# schematic.net
KiCad netlist of a schematic drawn in Altium Designer
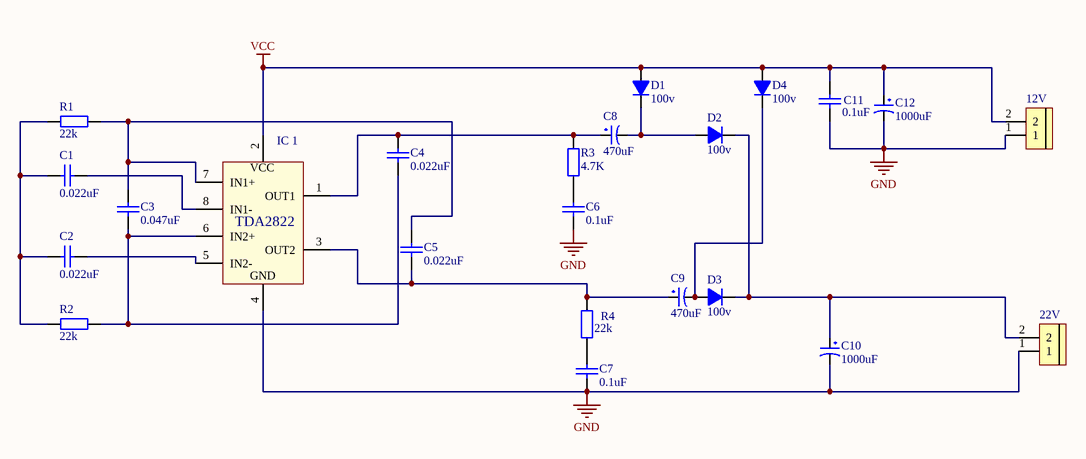
[diagram p0: schematic.SchDoc]

(export (version "E")
  (design (tool "Eeschema 10.0.6"))
  (components
    (comp (ref "12V")
      (value "~")
      (footprint "Con 2 KF301 5.08")
      (description "Cắm")
      (libsource (lib "Connector") (part "CON 2 KF301"))
    )
    (comp (ref "22V")
      (value "~")
      (footprint "Con 2 KF301 5.08")
      (description "Cắm")
      (libsource (lib "Connector") (part "CON 2 KF301"))
    )
    (comp (ref "C1")
      (value "0.022uF")
      (footprint "tu gom")
      (description "Cắm")
      (libsource (lib "Capacitor") (part "Tu gom 104 50V"))
    )
    (comp (ref "C2")
      (value "0.022uF")
      (footprint "tu gom")
      (description "Cắm")
      (libsource (lib "Capacitor") (part "Tu gom 104 50V"))
    )
    (comp (ref "C3")
      (value "0.047uF")
      (footprint "tu gom")
      (description "Cắm")
      (libsource (lib "Capacitor") (part "Tu gom 104 50V"))
    )
    (comp (ref "C4")
      (value "0.022uF")
      (footprint "tu gom")
      (description "Cắm")
      (libsource (lib "Capacitor") (part "Tu gom 104 50V"))
    )
    (comp (ref "C5")
      (value "0.022uF")
      (footprint "tu gom")
      (description "Cắm")
      (libsource (lib "Capacitor") (part "Tu gom 104 50V"))
    )
    (comp (ref "C6")
      (value "0.1uF")
      (footprint "tu gom")
      (description "Cắm")
      (libsource (lib "Capacitor") (part "Tu gom 104 50V"))
    )
    (comp (ref "C7")
      (value "0.1uF")
      (footprint "tu gom")
      (description "Cắm")
      (libsource (lib "Capacitor") (part "Tu gom 104 50V"))
    )
    (comp (ref "C8")
      (value "470uF")
      (footprint "tu hoa 13mm")
      (description "Cắm")
      (libsource (lib "") (part "Tu Hoa 1000uF 50V 13x26_1"))
    )
    (comp (ref "C9")
      (value "470uF")
      (footprint "tu hoa 13mm")
      (description "Cắm")
      (libsource (lib "") (part "Tu Hoa 1000uF 50V 13x26_1"))
    )
    (comp (ref "C10")
      (value "1000uF")
      (footprint "tu hoa 13mm")
      (description "Cắm")
      (libsource (lib "Capacitor") (part "Tu Hoa 1000uF 50V 13x26"))
    )
    (comp (ref "C11")
      (value "0.1uF")
      (footprint "tu gom")
      (description "Cắm")
      (libsource (lib "Capacitor") (part "Tu gom 104 50V"))
    )
    (comp (ref "C12")
      (value "1000uF")
      (footprint "tu hoa 13mm")
      (description "Cắm")
      (libsource (lib "Capacitor") (part "Tu Hoa 1000uF 50V 13x26"))
    )
    (comp (ref "D1")
      (value "100v")
      (footprint "DIODE 1A")
      (description "Cắm")
      (libsource (lib "Diode") (part "Diode 1N4007"))
    )
    (comp (ref "D2")
      (value "100v")
      (footprint "DIODE 1A")
      (description "Cắm")
      (libsource (lib "Diode") (part "Diode 1N4007"))
    )
    (comp (ref "D3")
      (value "100v")
      (footprint "DIODE 1A")
      (description "Cắm")
      (libsource (lib "Diode") (part "Diode 1N4007"))
    )
    (comp (ref "D4")
      (value "100v")
      (footprint "DIODE 1A")
      (description "Cắm")
      (libsource (lib "Diode") (part "Diode 1N4007"))
    )
    (comp (ref "IC 1")
      (value "MH001571")
      (footprint "DIP8")
      (description "Cắm")
      (libsource (lib "IC") (part "TDA2822 DIP"))
    )
    (comp (ref "R1")
      (value "22k")
      (footprint "tro vach 1/4w")
      (description "Cắm")
      (libsource (lib "Resistor") (part "Tro Vach 1/4W 5% 22k"))
    )
    (comp (ref "R2")
      (value "22k")
      (footprint "tro vach 1/4w")
      (description "Cắm")
      (libsource (lib "Resistor") (part "Tro Vach 1/4W 5% 22k"))
    )
    (comp (ref "R3")
      (value "4.7K")
      (footprint "tro vach 1/4w")
      (description "Cắm")
      (libsource (lib "Resistor") (part "Tro Vach 1/4W 5% 22k"))
    )
    (comp (ref "R4")
      (value "22k")
      (footprint "tro vach 1/4w")
      (description "Cắm")
      (libsource (lib "Resistor") (part "Tro Vach 1/4W 5% 22k"))
    )
  )
  (nets
    (net (code "1") (name "GND") (class "Default")
      (node (ref "12V") (pin "1") (pinfunction "1_1") (pintype "passive"))
      (node (ref "22V") (pin "1") (pinfunction "1_1") (pintype "passive"))
      (node (ref "C10") (pin "2") (pinfunction "2_2") (pintype "passive"))
      (node (ref "C11") (pin "2") (pinfunction "2_2") (pintype "passive"))
      (node (ref "C12") (pin "2") (pinfunction "2_2") (pintype "passive"))
      (node (ref "C6") (pin "2") (pinfunction "2_2") (pintype "passive"))
      (node (ref "C7") (pin "2") (pinfunction "2_2") (pintype "passive"))
      (node (ref "IC 1") (pin "4") (pinfunction "GND_4") (pintype "passive"))
    )
    (net (code "2") (name "Net-(C1-Pad2)") (class "Default")
      (node (ref "C1") (pin "2") (pinfunction "2_2") (pintype "passive"))
      (node (ref "C2") (pin "2") (pinfunction "2_2") (pintype "passive"))
      (node (ref "R1") (pin "1") (pinfunction "1_1") (pintype "passive"))
      (node (ref "R2") (pin "1") (pinfunction "1_1") (pintype "passive"))
    )
    (net (code "3") (name "Net-(C6-Pad1)") (class "Default")
      (node (ref "C6") (pin "1") (pinfunction "1_1") (pintype "passive"))
      (node (ref "R3") (pin "1") (pinfunction "1_1") (pintype "passive"))
    )
    (net (code "4") (name "Net-(C7-Pad1)") (class "Default")
      (node (ref "C7") (pin "1") (pinfunction "1_1") (pintype "passive"))
      (node (ref "R4") (pin "1") (pinfunction "1_1") (pintype "passive"))
    )
    (net (code "5") (name "Net-(D1-K)") (class "Default")
      (node (ref "C8") (pin "2") (pinfunction "2_2") (pintype "passive"))
      (node (ref "D1") (pin "2") (pinfunction "K_2") (pintype "passive"))
      (node (ref "D2") (pin "1") (pinfunction "A_1") (pintype "passive"))
    )
    (net (code "6") (name "Net-(D2-K)") (class "Default")
      (node (ref "22V") (pin "2") (pinfunction "2_2") (pintype "passive"))
      (node (ref "C10") (pin "1") (pinfunction "1_1") (pintype "passive"))
      (node (ref "D2") (pin "2") (pinfunction "K_2") (pintype "passive"))
      (node (ref "D3") (pin "2") (pinfunction "K_2") (pintype "passive"))
    )
    (net (code "7") (name "Net-(D3-A)") (class "Default")
      (node (ref "C9") (pin "2") (pinfunction "2_2") (pintype "passive"))
      (node (ref "D3") (pin "1") (pinfunction "A_1") (pintype "passive"))
      (node (ref "D4") (pin "2") (pinfunction "K_2") (pintype "passive"))
    )
    (net (code "8") (name "Net-(IC 1-IN1+)") (class "Default")
      (node (ref "C3") (pin "2") (pinfunction "2_2") (pintype "passive"))
      (node (ref "C5") (pin "1") (pinfunction "1_1") (pintype "passive"))
      (node (ref "IC 1") (pin "7") (pinfunction "IN1+_7") (pintype "passive"))
      (node (ref "R1") (pin "2") (pinfunction "2_2") (pintype "passive"))
    )
    (net (code "9") (name "Net-(IC 1-IN1-)") (class "Default")
      (node (ref "C1") (pin "1") (pinfunction "1_1") (pintype "passive"))
      (node (ref "IC 1") (pin "8") (pinfunction "IN1-_8") (pintype "passive"))
    )
    (net (code "10") (name "Net-(IC 1-IN2+)") (class "Default")
      (node (ref "C3") (pin "1") (pinfunction "1_1") (pintype "passive"))
      (node (ref "C4") (pin "2") (pinfunction "2_2") (pintype "passive"))
      (node (ref "IC 1") (pin "6") (pinfunction "IN2+_6") (pintype "passive"))
      (node (ref "R2") (pin "2") (pinfunction "2_2") (pintype "passive"))
    )
    (net (code "11") (name "Net-(IC 1-IN2-)") (class "Default")
      (node (ref "C2") (pin "1") (pinfunction "1_1") (pintype "passive"))
      (node (ref "IC 1") (pin "5") (pinfunction "IN2-_5") (pintype "passive"))
    )
    (net (code "12") (name "Net-(IC 1-OUT1)") (class "Default")
      (node (ref "C4") (pin "1") (pinfunction "1_1") (pintype "passive"))
      (node (ref "C8") (pin "1") (pinfunction "1_1") (pintype "passive"))
      (node (ref "IC 1") (pin "1") (pinfunction "OUT1_1") (pintype "passive"))
      (node (ref "R3") (pin "2") (pinfunction "2_2") (pintype "passive"))
    )
    (net (code "13") (name "Net-(IC 1-OUT2)") (class "Default")
      (node (ref "C5") (pin "2") (pinfunction "2_2") (pintype "passive"))
      (node (ref "C9") (pin "1") (pinfunction "1_1") (pintype "passive"))
      (node (ref "IC 1") (pin "3") (pinfunction "OUT2_3") (pintype "passive"))
      (node (ref "R4") (pin "2") (pinfunction "2_2") (pintype "passive"))
    )
    (net (code "14") (name "VCC") (class "Default")
      (node (ref "12V") (pin "2") (pinfunction "2_2") (pintype "passive"))
      (node (ref "C11") (pin "1") (pinfunction "1_1") (pintype "passive"))
      (node (ref "C12") (pin "1") (pinfunction "1_1") (pintype "passive"))
      (node (ref "D1") (pin "1") (pinfunction "A_1") (pintype "passive"))
      (node (ref "D4") (pin "1") (pinfunction "A_1") (pintype "passive"))
      (node (ref "IC 1") (pin "2") (pinfunction "VCC_2") (pintype "passive"))
    )
  )
)
